# Power.net
KiCad netlist of a schematic drawn in Altium Designer
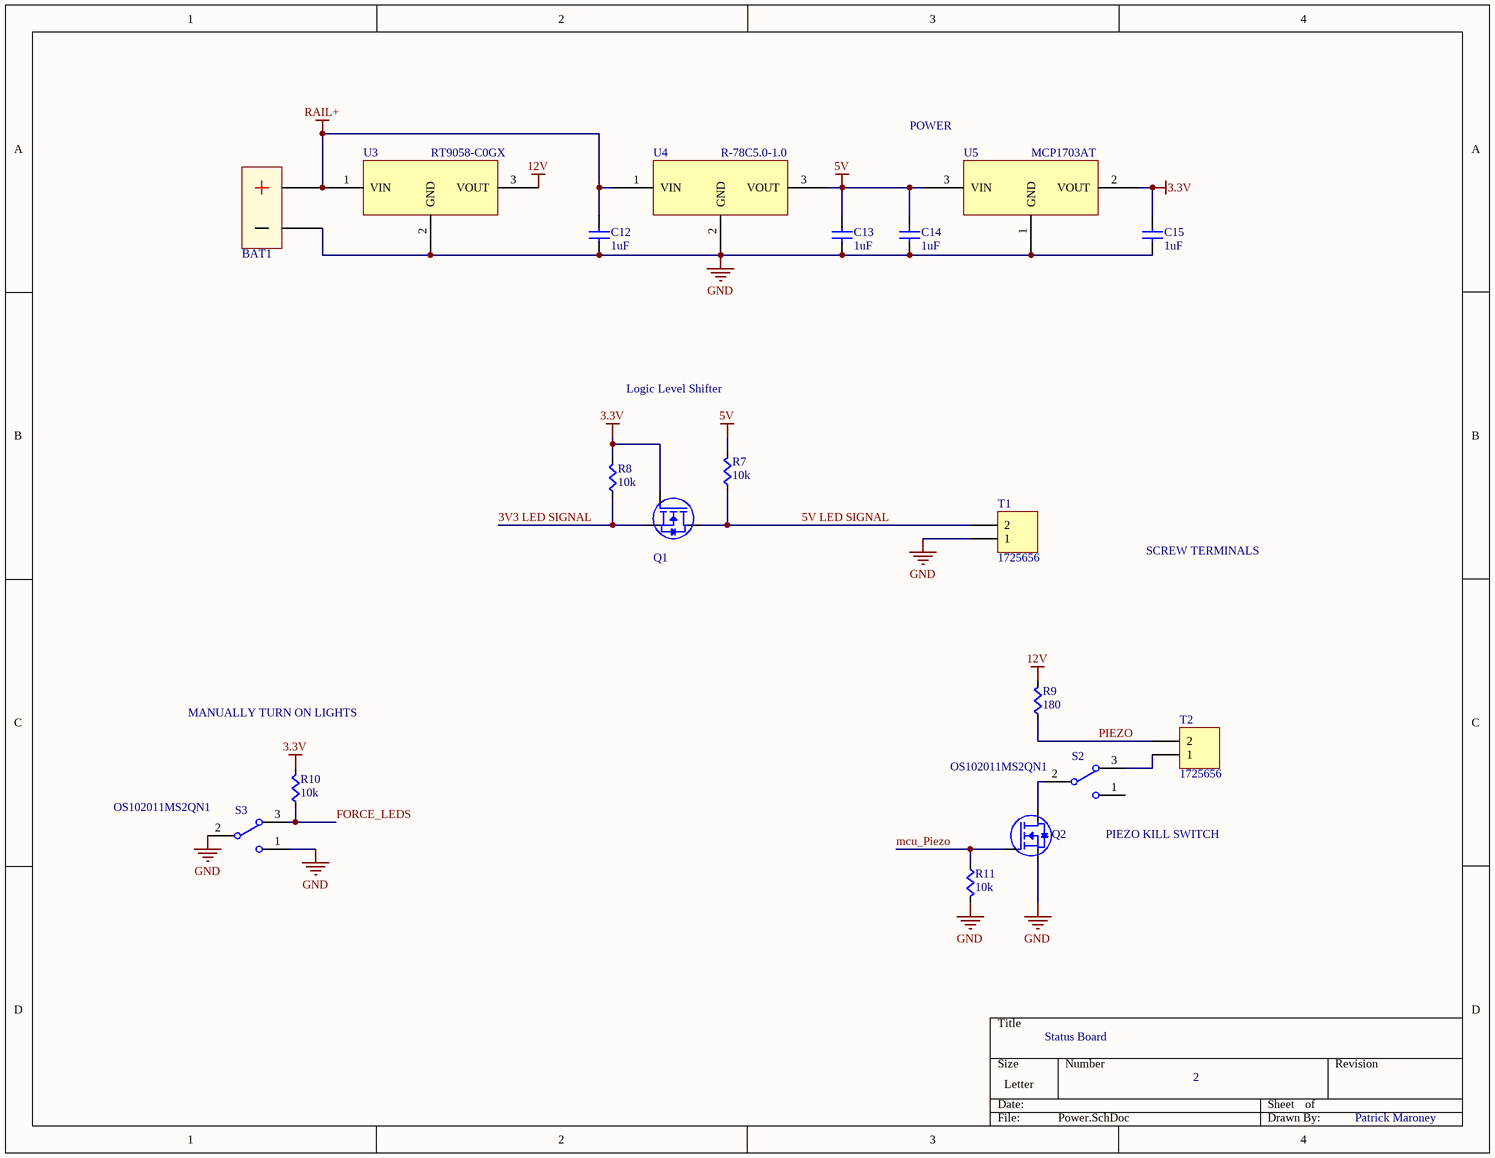
[diagram p0: Power.SchDoc]

(export (version "E")
  (design (tool "Eeschema 10.0.6"))
  (components
    (comp (ref "BAT1")
      (value "BATWIRE")
      (footprint "BATWIRE12")
      (description "Two large gauge leads soldered directly to the board.")
      (libsource (lib "SubjuGator8") (part "BATWIRE"))
    )
    (comp (ref "C12")
      (value "1uF")
      (footprint "CAPC0603")
      (fields (field (name "Comment") "Cap"))
      (libsource (lib "SubjuGator8") (part "Cap"))
    )
    (comp (ref "C13")
      (value "1uF")
      (footprint "CAPC0603")
      (fields (field (name "Comment") "Cap"))
      (libsource (lib "SubjuGator8") (part "Cap"))
    )
    (comp (ref "C14")
      (value "1uF")
      (footprint "CAPC0603")
      (fields (field (name "Comment") "Cap"))
      (libsource (lib "SubjuGator8") (part "Cap"))
    )
    (comp (ref "C15")
      (value "1uF")
      (footprint "CAPC0603")
      (fields (field (name "Comment") "Cap"))
      (libsource (lib "SubjuGator8") (part "Cap"))
    )
    (comp (ref "Q1")
      (value "BSS138")
      (footprint "BSS138")
      (description "MOSFET N-CH 50V 220MA SOT-23")
      (libsource (lib "SubjuGator8") (part "BSS138"))
    )
    (comp (ref "Q2")
      (value "TPCA8052-H(TE12LQM")
      (footprint "TPCA8052-H(TE12LQM")
      (description "MOSFET N-CH 40V 20A 8SOP")
      (libsource (lib "SubjuGator8") (part "TPCA8052-H"))
    )
    (comp (ref "R7")
      (value "10k")
      (footprint "RES0603")
      (fields (field (name "Comment") "Res"))
      (libsource (lib "SubjuGator8") (part "Res"))
    )
    (comp (ref "R8")
      (value "10k")
      (footprint "RES0603")
      (fields (field (name "Comment") "Res"))
      (libsource (lib "SubjuGator8") (part "Res"))
    )
    (comp (ref "R9")
      (value "180")
      (footprint "RES0603")
      (fields (field (name "Comment") "Res"))
      (libsource (lib "SubjuGator8") (part "Res"))
    )
    (comp (ref "R10")
      (value "10k")
      (footprint "RES0603")
      (fields (field (name "Comment") "Res"))
      (libsource (lib "SubjuGator8") (part "Res"))
    )
    (comp (ref "R11")
      (value "10k")
      (footprint "RES0603")
      (fields (field (name "Comment") "Res"))
      (libsource (lib "SubjuGator8") (part "Res"))
    )
    (comp (ref "S2")
      (value "OS102011MS2QN1")
      (footprint "OS102011MS2QN1")
      (description "SWITCH SLIDE SPDT 100MA 12V")
      (libsource (lib "SubjuGator8") (part "OS102011MS2QN1"))
    )
    (comp (ref "S3")
      (value "OS102011MS2QN1")
      (footprint "OS102011MS2QN1")
      (description "SWITCH SLIDE SPDT 100MA 12V")
      (libsource (lib "SubjuGator8") (part "OS102011MS2QN1"))
    )
    (comp (ref "T1")
      (value "1725656")
      (footprint "1725656")
      (description "CONN TERM BLOCK 2.54MM 2POS")
      (libsource (lib "SubjuGator8") (part "1725656"))
    )
    (comp (ref "T2")
      (value "1725656")
      (footprint "1725656")
      (description "CONN TERM BLOCK 2.54MM 2POS")
      (libsource (lib "SubjuGator8") (part "1725656"))
    )
    (comp (ref "U3")
      (value "RT9058-C0GX")
      (footprint "RT9058-C0GX")
      (description "IC REG LDO 12V 0.1A")
      (libsource (lib "SubjuGator8") (part "RT9058-C0GX"))
    )
    (comp (ref "U4")
      (value "R-78C5.0-1.0")
      (footprint "R-78C5.0-1.0")
      (description "CONV DC/DC 1A 5V OUT SIP VERT")
      (libsource (lib "SubjuGator8") (part "R-78C5.0-1.0"))
    )
    (comp (ref "U5")
      (value "MCP1703AT")
      (footprint "MCP1703AT-xx02EDB")
      (description "250 mA, 16V, Low Quiescent Current LDO Regulator")
      (libsource (lib "SubjuGator8") (part "MCP1703AT"))
    )
  )
  (nets
    (net (code "1") (name "/3V3 LED SIGNAL") (class "Default")
      (node (ref "Q1") (pin "S") (pinfunction "S_S") (pintype "passive"))
      (node (ref "R8") (pin "2") (pinfunction "B_2") (pintype "passive"))
    )
    (net (code "2") (name "/5V LED SIGNAL") (class "Default")
      (node (ref "Q1") (pin "D") (pinfunction "D_D") (pintype "passive"))
      (node (ref "R7") (pin "2") (pinfunction "B_2") (pintype "passive"))
      (node (ref "T1") (pin "2") (pinfunction "2_2") (pintype "passive"))
    )
    (net (code "3") (name "/FORCE_LEDS") (class "Default")
      (node (ref "R10") (pin "2") (pinfunction "B_2") (pintype "passive"))
      (node (ref "S3") (pin "3") (pinfunction "3_3") (pintype "passive"))
    )
    (net (code "4") (name "/PIEZO") (class "Default")
      (node (ref "R9") (pin "2") (pinfunction "B_2") (pintype "passive"))
      (node (ref "T2") (pin "2") (pinfunction "2_2") (pintype "passive"))
    )
    (net (code "5") (name "/mcu_Piezo") (class "Default")
      (node (ref "Q2") (pin "G") (pinfunction "G_G") (pintype "passive"))
      (node (ref "R11") (pin "2") (pinfunction "B_2") (pintype "passive"))
    )
    (net (code "6") (name "3.3V") (class "Default")
      (node (ref "C15") (pin "1") (pinfunction "A_1") (pintype "passive"))
      (node (ref "Q1") (pin "G") (pinfunction "G_G") (pintype "passive"))
      (node (ref "R10") (pin "1") (pinfunction "A_1") (pintype "passive"))
      (node (ref "R8") (pin "1") (pinfunction "A_1") (pintype "passive"))
      (node (ref "U5") (pin "2") (pinfunction "VOUT_2") (pintype "passive"))
    )
    (net (code "7") (name "5V") (class "Default")
      (node (ref "C13") (pin "1") (pinfunction "A_1") (pintype "passive"))
      (node (ref "C14") (pin "1") (pinfunction "A_1") (pintype "passive"))
      (node (ref "R7") (pin "1") (pinfunction "A_1") (pintype "passive"))
      (node (ref "U4") (pin "3") (pinfunction "VOUT_3") (pintype "passive"))
      (node (ref "U5") (pin "3") (pinfunction "VIN_3") (pintype "passive"))
    )
    (net (code "8") (name "12V") (class "Default")
      (node (ref "R9") (pin "1") (pinfunction "A_1") (pintype "passive"))
      (node (ref "U3") (pin "3") (pinfunction "VOUT_3") (pintype "passive"))
    )
    (net (code "9") (name "GND") (class "Default")
      (node (ref "BAT1") (pin "-") (pinfunction "-_-") (pintype "power_in"))
      (node (ref "C12") (pin "2") (pinfunction "B_2") (pintype "passive"))
      (node (ref "C13") (pin "2") (pinfunction "B_2") (pintype "passive"))
      (node (ref "C14") (pin "2") (pinfunction "B_2") (pintype "passive"))
      (node (ref "C15") (pin "2") (pinfunction "B_2") (pintype "passive"))
      (node (ref "Q2") (pin "S") (pinfunction "S_S") (pintype "passive"))
      (node (ref "R11") (pin "1") (pinfunction "A_1") (pintype "passive"))
      (node (ref "S3") (pin "1") (pinfunction "1_1") (pintype "passive"))
      (node (ref "S3") (pin "2") (pinfunction "2_2") (pintype "passive"))
      (node (ref "T1") (pin "1") (pinfunction "1_1") (pintype "passive"))
      (node (ref "U3") (pin "2") (pinfunction "GND_2") (pintype "power_in"))
      (node (ref "U4") (pin "2") (pinfunction "GND_2") (pintype "power_in"))
      (node (ref "U5") (pin "1") (pinfunction "GND_1") (pintype "power_in"))
    )
    (net (code "10") (name "Net-(Q2-PadD)") (class "Default")
      (node (ref "Q2") (pin "D") (pinfunction "D_D") (pintype "passive"))
      (node (ref "S2") (pin "2") (pinfunction "2_2") (pintype "passive"))
    )
    (net (code "11") (name "Net-(S2-Pad3)") (class "Default")
      (node (ref "S2") (pin "3") (pinfunction "3_3") (pintype "passive"))
      (node (ref "T2") (pin "1") (pinfunction "1_1") (pintype "passive"))
    )
    (net (code "12") (name "RAIL+") (class "Default")
      (node (ref "BAT1") (pin "+") (pinfunction "+_+") (pintype "power_in"))
      (node (ref "C12") (pin "1") (pinfunction "A_1") (pintype "passive"))
      (node (ref "U3") (pin "1") (pinfunction "VIN_1") (pintype "passive"))
      (node (ref "U4") (pin "1") (pinfunction "VIN_1") (pintype "passive"))
    )
    (net (code "13") (name "unconnected-(S2-Pad1)") (class "Default")
      (node (ref "S2") (pin "1") (pinfunction "1_1") (pintype "passive"))
    )
  )
)
